# jetsonToServoBuffer.net
KiCad netlist of a schematic drawn in EAGLE
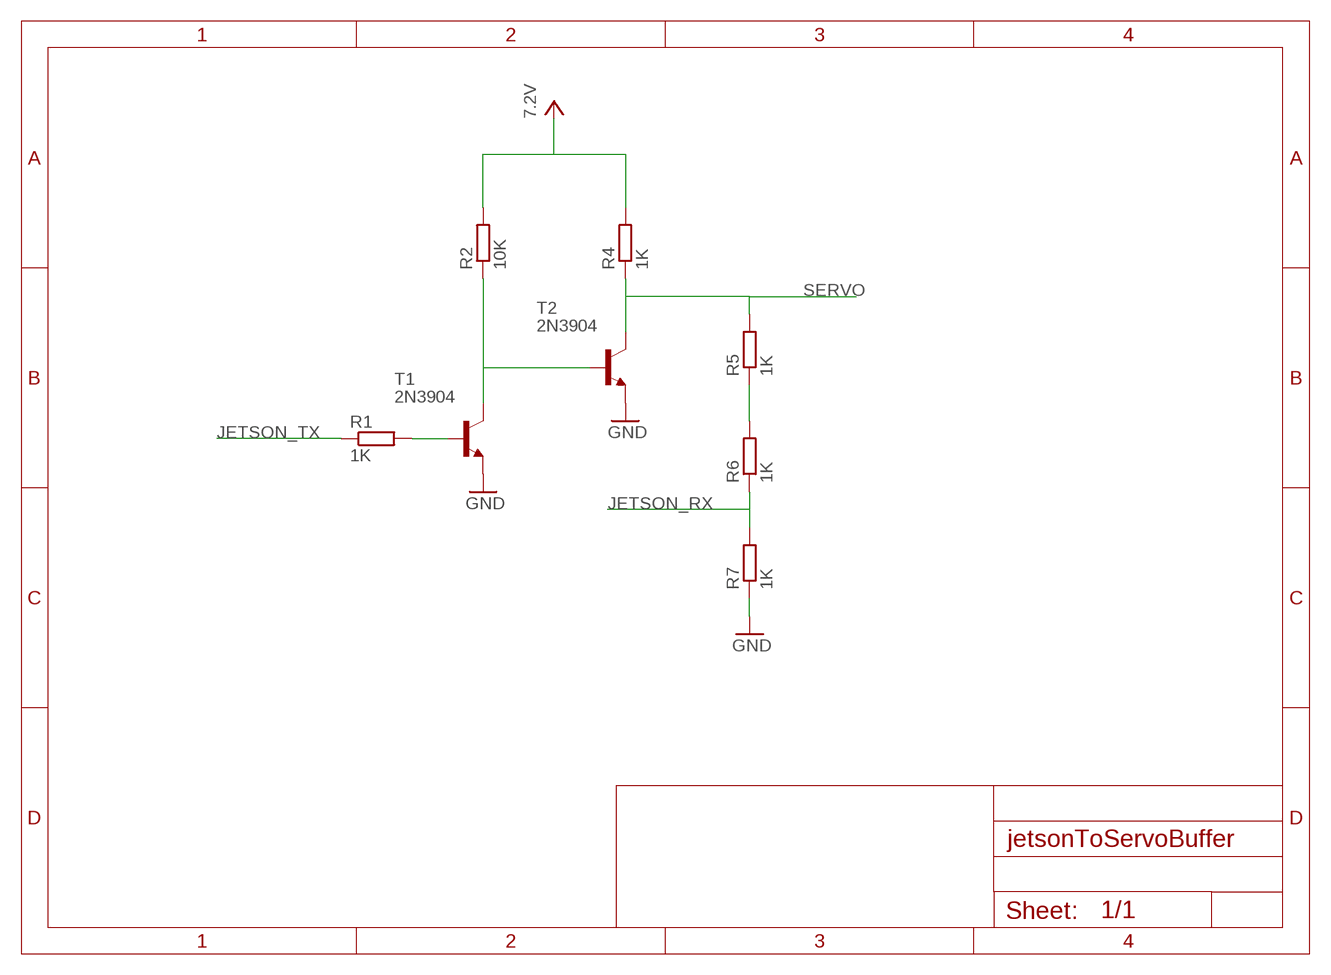
[diagram p0: schematic, sheet 1]

(export (version "E")
  (design (tool "Eeschema 10.0.6"))
  (components
    (comp (ref "R1")
      (value "1K")
      (footprint "eagle-import:0309_10")
      (libsource (lib "eagle-import") (part "R-EU_0309/10"))
    )
    (comp (ref "R2")
      (value "10K")
      (footprint "eagle-import:0309_10")
      (libsource (lib "eagle-import") (part "R-EU_0309/10"))
    )
    (comp (ref "R4")
      (value "1K")
      (footprint "eagle-import:0309_10")
      (libsource (lib "eagle-import") (part "R-EU_0309/10"))
    )
    (comp (ref "R5")
      (value "1K")
      (footprint "eagle-import:0309_10")
      (libsource (lib "eagle-import") (part "R-EU_0309/10"))
    )
    (comp (ref "R6")
      (value "1K")
      (footprint "eagle-import:0309_10")
      (libsource (lib "eagle-import") (part "R-EU_0309/10"))
    )
    (comp (ref "R7")
      (value "1K")
      (footprint "eagle-import:0309_10")
      (libsource (lib "eagle-import") (part "R-EU_0309/10"))
    )
    (comp (ref "T1")
      (value "2N3904")
      (footprint "eagle-import:TO92")
      (libsource (lib "eagle-import") (part "2N3904"))
    )
    (comp (ref "T2")
      (value "2N3904")
      (footprint "eagle-import:TO92")
      (libsource (lib "eagle-import") (part "2N3904"))
    )
  )
  (nets
    (net (code "1") (name "/JETSON_RX") (class "Default")
      (node (ref "R6") (pin "1") (pinfunction "1_1") (pintype "passive"))
      (node (ref "R7") (pin "2") (pinfunction "2_2") (pintype "passive"))
    )
    (net (code "2") (name "/JETSON_TX") (class "Default")
      (node (ref "R1") (pin "1") (pinfunction "1_1") (pintype "passive"))
    )
    (net (code "3") (name "/SERVO") (class "Default")
      (node (ref "R4") (pin "1") (pinfunction "1_1") (pintype "passive"))
      (node (ref "R5") (pin "2") (pinfunction "2_2") (pintype "passive"))
      (node (ref "T2") (pin "1") (pinfunction "C_1") (pintype "passive"))
    )
    (net (code "4") (name "7.2V") (class "Default")
      (node (ref "R2") (pin "2") (pinfunction "2_2") (pintype "passive"))
      (node (ref "R4") (pin "2") (pinfunction "2_2") (pintype "passive"))
    )
    (net (code "5") (name "GND") (class "Default")
      (node (ref "R7") (pin "1") (pinfunction "1_1") (pintype "passive"))
      (node (ref "T1") (pin "3") (pinfunction "E_3") (pintype "passive"))
      (node (ref "T2") (pin "3") (pinfunction "E_3") (pintype "passive"))
    )
    (net (code "6") (name "Net-(R5-Pad1)") (class "Default")
      (node (ref "R5") (pin "1") (pinfunction "1_1") (pintype "passive"))
      (node (ref "R6") (pin "2") (pinfunction "2_2") (pintype "passive"))
    )
    (net (code "7") (name "Net-(T1-B)") (class "Default")
      (node (ref "R1") (pin "2") (pinfunction "2_2") (pintype "passive"))
      (node (ref "T1") (pin "2") (pinfunction "B_2") (pintype "passive"))
    )
    (net (code "8") (name "Net-(T1-C)") (class "Default")
      (node (ref "R2") (pin "1") (pinfunction "1_1") (pintype "passive"))
      (node (ref "T1") (pin "1") (pinfunction "C_1") (pintype "passive"))
      (node (ref "T2") (pin "2") (pinfunction "B_2") (pintype "passive"))
    )
  )
)
